# Main_Board_Tank.net
KiCad netlist of a schematic drawn in Altium Designer
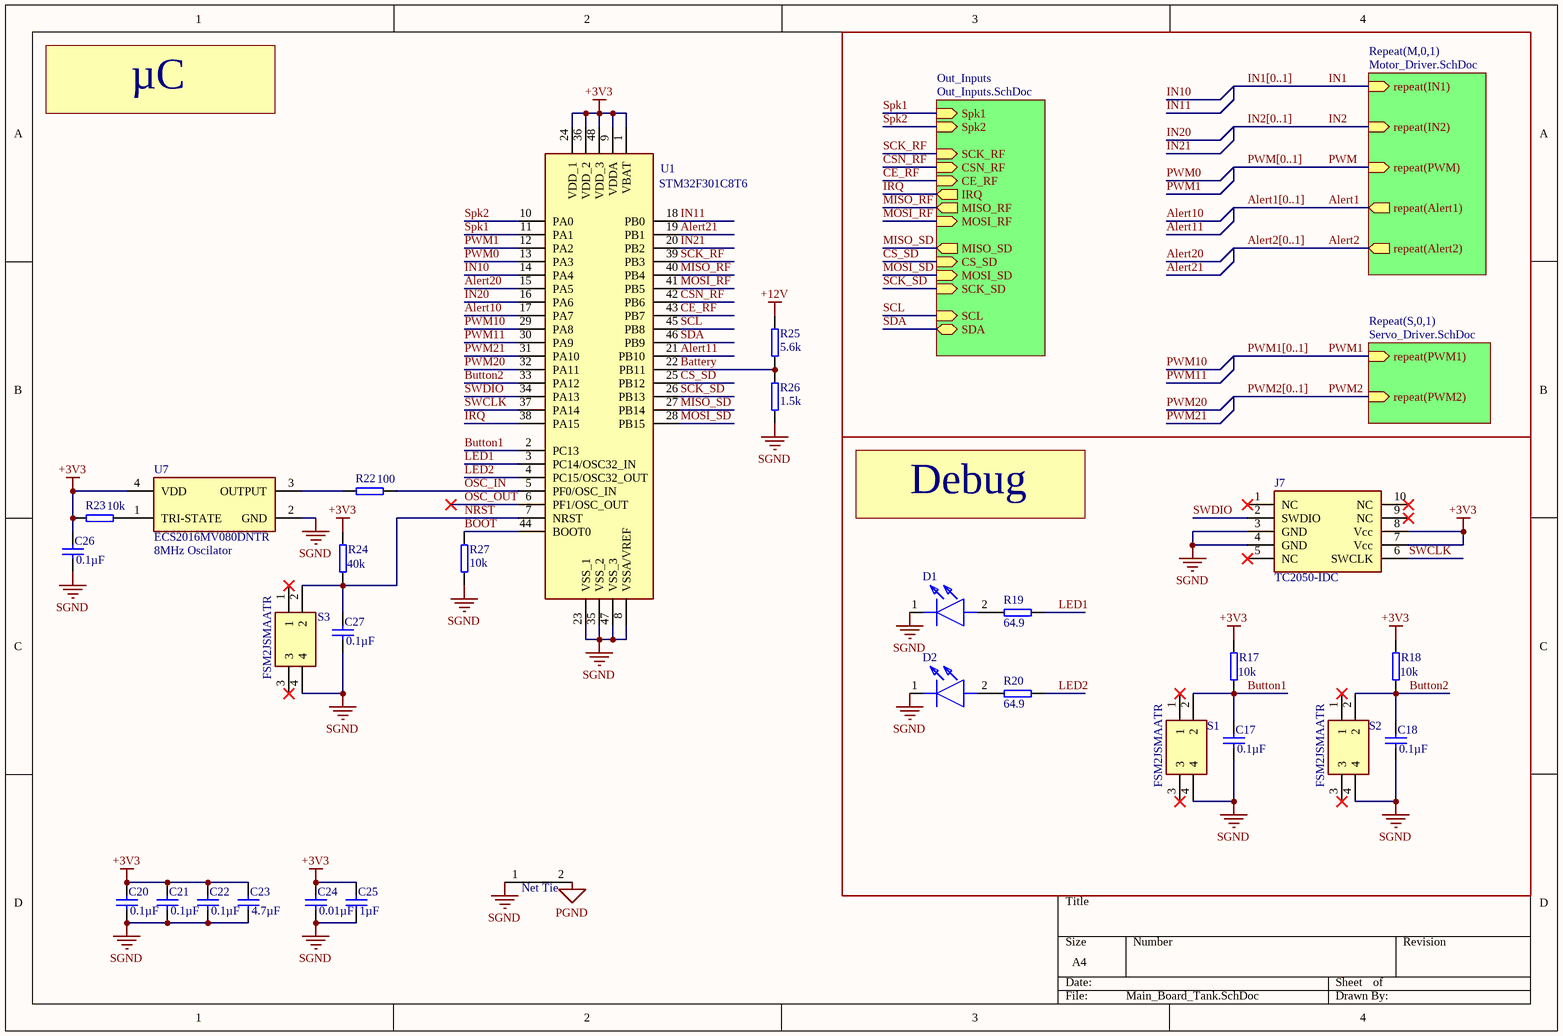
[diagram p0: Main_Board_Tank.SchDoc]

(export (version "E")
  (design (tool "Eeschema 10.0.6"))
  (components
    (comp (ref "C17")
      (value "0.1µF")
      (footprint "Capacitor 0603")
      (description "Capacitor")
      (libsource (lib "Schematic_Lib") (part "Capacitor 0603"))
    )
    (comp (ref "C18")
      (value "0.1µF")
      (footprint "Capacitor 0603")
      (description "Capacitor")
      (libsource (lib "Schematic_Lib") (part "Capacitor 0603"))
    )
    (comp (ref "C20")
      (value "0.1µF")
      (footprint "Capacitor 0603")
      (description "Capacitor")
      (libsource (lib "Schematic_Lib") (part "Capacitor 0603"))
    )
    (comp (ref "C21")
      (value "0.1µF")
      (footprint "Capacitor 0603")
      (description "Capacitor")
      (libsource (lib "Schematic_Lib") (part "Capacitor 0603"))
    )
    (comp (ref "C22")
      (value "0.1µF")
      (footprint "Capacitor 0603")
      (description "Capacitor")
      (libsource (lib "Schematic_Lib") (part "Capacitor 0603"))
    )
    (comp (ref "C23")
      (value "4.7µF")
      (footprint "Capacitor 0603")
      (description "Capacitor")
      (libsource (lib "Schematic_Lib") (part "Capacitor 0603"))
    )
    (comp (ref "C24")
      (value "0.01µF")
      (footprint "Capacitor 0603")
      (description "Capacitor")
      (libsource (lib "Schematic_Lib") (part "Capacitor 0603"))
    )
    (comp (ref "C25")
      (value "1µF")
      (footprint "Capacitor 0603")
      (description "Capacitor")
      (libsource (lib "Schematic_Lib") (part "Capacitor 0603"))
    )
    (comp (ref "C26")
      (value "0.1µF")
      (footprint "Capacitor 0603")
      (description "Capacitor")
      (libsource (lib "Schematic_Lib") (part "Capacitor 0603"))
    )
    (comp (ref "C27")
      (value "0.1µF")
      (footprint "Capacitor 0603")
      (description "Capacitor")
      (libsource (lib "Schematic_Lib") (part "Capacitor 0603"))
    )
    (comp (ref "D1")
      (value "LED 1608 (0603) SMD")
      (footprint "INS21AT2G")
      (libsource (lib "Schematic_Lib") (part "LED 1608 (0603) SMD"))
    )
    (comp (ref "D2")
      (value "LED 1608 (0603) SMD")
      (footprint "INS21AT2G")
      (libsource (lib "Schematic_Lib") (part "LED 1608 (0603) SMD"))
    )
    (comp (ref "J7")
      (value "TC2050-IDC")
      (footprint "TAG-CONNECT_TC2050-IDC")
      (description "CBL PLUG-OF-NAILS 10-PIN W/LEGS")
      (fields (field (name "MF") "Tag-Connect LLC") (field (name "DIGI-KEY_PART_NUMBER") "TC2050-IDC-ND"))
      (libsource (lib "Schematic_Lib") (part "TC2050-IDC"))
    )
    (comp (ref "NT1")
      (value "Net Tie")
      (footprint "Net_Tie")
      (libsource (lib "Schematic_Lib") (part "Net Tie"))
    )
    (comp (ref "R17")
      (value "10k")
      (footprint "Resistor 0603")
      (description "Resistor")
      (libsource (lib "Schematic_Lib") (part "Resistor 0603"))
    )
    (comp (ref "R18")
      (value "10k")
      (footprint "Resistor 0603")
      (description "Resistor")
      (libsource (lib "Schematic_Lib") (part "Resistor 0603"))
    )
    (comp (ref "R19")
      (value "64.9")
      (footprint "Resistor 0603")
      (description "Resistor")
      (libsource (lib "Schematic_Lib") (part "Resistor 0603"))
    )
    (comp (ref "R20")
      (value "64.9")
      (footprint "Resistor 0603")
      (description "Resistor")
      (libsource (lib "Schematic_Lib") (part "Resistor 0603"))
    )
    (comp (ref "R22")
      (value "100")
      (footprint "Resistor 0603")
      (description "Resistor")
      (libsource (lib "Schematic_Lib") (part "Resistor 0603"))
    )
    (comp (ref "R23")
      (value "10k")
      (footprint "Resistor 0603")
      (description "Resistor")
      (libsource (lib "Schematic_Lib") (part "Resistor 0603"))
    )
    (comp (ref "R24")
      (value "40k")
      (footprint "Resistor 0603")
      (description "Resistor")
      (libsource (lib "Schematic_Lib") (part "Resistor 0603"))
    )
    (comp (ref "R25")
      (value "5.6k")
      (footprint "Resistor 0603")
      (description "Resistor")
      (libsource (lib "Schematic_Lib") (part "Resistor 0603"))
    )
    (comp (ref "R26")
      (value "1.5k")
      (footprint "Resistor 0603")
      (description "Resistor")
      (libsource (lib "Schematic_Lib") (part "Resistor 0603"))
    )
    (comp (ref "R27")
      (value "10k")
      (footprint "Resistor 0603")
      (description "Resistor")
      (libsource (lib "Schematic_Lib") (part "Resistor 0603"))
    )
    (comp (ref "S1")
      (value "FSM2JSMAATR")
      (footprint "FSM2J_1")
      (description "Switch")
      (fields (field (name "MOUSER PART NUMBER") "506-FSM2JSMAATR"))
      (libsource (lib "Schematic_Lib") (part "FSM2JSMAATR"))
    )
    (comp (ref "S2")
      (value "FSM2JSMAATR")
      (footprint "FSM2J_1")
      (description "Switch")
      (fields (field (name "MOUSER PART NUMBER") "506-FSM2JSMAATR"))
      (libsource (lib "Schematic_Lib") (part "FSM2JSMAATR"))
    )
    (comp (ref "S3")
      (value "FSM2JSMAATR")
      (footprint "FSM2J_1")
      (description "Switch")
      (fields (field (name "MOUSER PART NUMBER") "506-FSM2JSMAATR"))
      (libsource (lib "Schematic_Lib") (part "FSM2JSMAATR"))
    )
    (comp (ref "U1")
      (value "STM32F301C8T6")
      (footprint "QFP50P900X900X160-48N")
      (description "STMICROELECTRONICS - STM32F301C8T6 - MCU, 32BIT, CORTEX-M4, 72MHZ, LQFP-48")
      (fields (field (name "MOUSER PART NUMBER") "511-STM32F301C8T6"))
      (libsource (lib "Schematic_Lib") (part "STM32F301C8T6"))
    )
    (comp (ref "U7")
      (value "ECS2016MV080DNTR")
      (footprint "OSC_ECS-1618-300-BN-TR")
      (description "25 MHz XO (Standard) HCMOS Oscillator 1.8V ~ 3.3V Enable/Disable 4-SMD, No Lead")
      (fields (field (name "MF") "ECS Inc.") (field (name "MP") "ECS-2016MV-250-CN-TR3"))
      (libsource (lib "Schematic_Lib") (part "ECS-2016MV-250-CN-TR3"))
    )
  )
  (nets
    (net (code "1") (name "+3V3") (class "Default")
      (node (ref "C20") (pin "1") (pinfunction "1_1") (pintype "passive"))
      (node (ref "C21") (pin "1") (pinfunction "1_1") (pintype "passive"))
      (node (ref "C22") (pin "1") (pinfunction "1_1") (pintype "passive"))
      (node (ref "C23") (pin "1") (pinfunction "1_1") (pintype "passive"))
      (node (ref "C24") (pin "1") (pinfunction "1_1") (pintype "passive"))
      (node (ref "C25") (pin "1") (pinfunction "1_1") (pintype "passive"))
      (node (ref "C26") (pin "1") (pinfunction "1_1") (pintype "passive"))
      (node (ref "J7") (pin "7") (pinfunction "Vcc_7") (pintype "passive"))
      (node (ref "J7") (pin "8") (pinfunction "Vcc_8") (pintype "passive"))
      (node (ref "R17") (pin "1") (pintype "passive"))
      (node (ref "R18") (pin "1") (pintype "passive"))
      (node (ref "R23") (pin "2") (pintype "passive"))
      (node (ref "R24") (pin "1") (pintype "passive"))
      (node (ref "U1") (pin "1") (pinfunction "VBAT_1") (pintype "passive"))
      (node (ref "U1") (pin "24") (pinfunction "VDD_1_24") (pintype "passive"))
      (node (ref "U1") (pin "36") (pinfunction "VDD_2_36") (pintype "passive"))
      (node (ref "U1") (pin "48") (pinfunction "VDD_3_48") (pintype "passive"))
      (node (ref "U1") (pin "9") (pinfunction "VDDA_9") (pintype "passive"))
      (node (ref "U7") (pin "4") (pinfunction "VDD_4") (pintype "passive"))
    )
    (net (code "2") (name "+12V") (class "Default") (node (ref "R25") (pin "2") (pintype "passive")))
    (net (code "7") (name "/Alert10") (class "Default")
      (node (ref "U1") (pin "17") (pinfunction "PA7_17") (pintype "passive"))
    )
    (net (code "8") (name "/Alert11") (class "Default")
      (node (ref "U1") (pin "21") (pinfunction "PB10_21") (pintype "passive"))
    )
    (net (code "9") (name "/Alert20") (class "Default")
      (node (ref "U1") (pin "15") (pinfunction "PA5_15") (pintype "passive"))
    )
    (net (code "10") (name "/Alert21") (class "Default")
      (node (ref "U1") (pin "19") (pinfunction "PB1_19") (pintype "passive"))
    )
    (net (code "11") (name "/BOOT") (class "Default")
      (node (ref "R27") (pin "2") (pintype "passive"))
      (node (ref "U1") (pin "44") (pinfunction "BOOT0_44") (pintype "passive"))
    )
    (net (code "12") (name "/Battery") (class "Default")
      (node (ref "R25") (pin "1") (pintype "passive"))
      (node (ref "R26") (pin "2") (pintype "passive"))
      (node (ref "U1") (pin "22") (pinfunction "PB11_22") (pintype "passive"))
    )
    (net (code "13") (name "/Button1") (class "Default")
      (node (ref "C17") (pin "1") (pinfunction "1_1") (pintype "passive"))
      (node (ref "R17") (pin "2") (pintype "passive"))
      (node (ref "S1") (pin "2") (pinfunction "2_2") (pintype "passive"))
      (node (ref "U1") (pin "2") (pinfunction "PC13_2") (pintype "passive"))
    )
    (net (code "14") (name "/Button2") (class "Default")
      (node (ref "C18") (pin "1") (pinfunction "1_1") (pintype "passive"))
      (node (ref "R18") (pin "2") (pintype "passive"))
      (node (ref "S2") (pin "2") (pinfunction "2_2") (pintype "passive"))
      (node (ref "U1") (pin "33") (pinfunction "PA12_33") (pintype "passive"))
    )
    (net (code "15") (name "/CE_RF") (class "Default")
      (node (ref "U1") (pin "43") (pinfunction "PB7_43") (pintype "passive"))
    )
    (net (code "16") (name "/CSN_RF") (class "Default")
      (node (ref "U1") (pin "42") (pinfunction "PB6_42") (pintype "passive"))
    )
    (net (code "17") (name "/CS_SD") (class "Default")
      (node (ref "U1") (pin "25") (pinfunction "PB12_25") (pintype "passive"))
    )
    (net (code "22") (name "/IN10") (class "Default")
      (node (ref "U1") (pin "14") (pinfunction "PA4_14") (pintype "passive"))
    )
    (net (code "23") (name "/IN11") (class "Default")
      (node (ref "U1") (pin "18") (pinfunction "PB0_18") (pintype "passive"))
    )
    (net (code "24") (name "/IN20") (class "Default")
      (node (ref "U1") (pin "16") (pinfunction "PA6_16") (pintype "passive"))
    )
    (net (code "25") (name "/IN21") (class "Default")
      (node (ref "U1") (pin "20") (pinfunction "PB2_20") (pintype "passive"))
    )
    (net (code "26") (name "/IRQ") (class "Default")
      (node (ref "U1") (pin "38") (pinfunction "PA15_38") (pintype "passive"))
    )
    (net (code "27") (name "/LED1") (class "Default")
      (node (ref "R19") (pin "1") (pintype "passive"))
      (node (ref "U1") (pin "3") (pinfunction "PC14/OSC32_IN_3") (pintype "passive"))
    )
    (net (code "28") (name "/LED2") (class "Default")
      (node (ref "R20") (pin "1") (pintype "passive"))
      (node (ref "U1") (pin "4") (pinfunction "PC15/OSC32_OUT_4") (pintype "passive"))
    )
    (net (code "29") (name "/MISO_RF") (class "Default")
      (node (ref "U1") (pin "40") (pinfunction "PB4_40") (pintype "passive"))
    )
    (net (code "30") (name "/MISO_SD") (class "Default")
      (node (ref "U1") (pin "27") (pinfunction "PB14_27") (pintype "passive"))
    )
    (net (code "31") (name "/MOSI_RF") (class "Default")
      (node (ref "U1") (pin "41") (pinfunction "PB5_41") (pintype "passive"))
    )
    (net (code "32") (name "/MOSI_SD") (class "Default")
      (node (ref "U1") (pin "28") (pinfunction "PB15_28") (pintype "passive"))
    )
    (net (code "33") (name "/NRST") (class "Default")
      (node (ref "C27") (pin "1") (pinfunction "1_1") (pintype "passive"))
      (node (ref "R24") (pin "2") (pintype "passive"))
      (node (ref "S3") (pin "2") (pinfunction "2_2") (pintype "passive"))
      (node (ref "U1") (pin "7") (pinfunction "NRST_7") (pintype "passive"))
    )
    (net (code "34") (name "/OSC_IN") (class "Default")
      (node (ref "R22") (pin "1") (pintype "passive"))
      (node (ref "U1") (pin "5") (pinfunction "PF0/OSC_IN_5") (pintype "passive"))
    )
    (net (code "35") (name "/OSC_OUT") (class "Default")
      (node (ref "U1") (pin "6") (pinfunction "PF1/OSC_OUT_6") (pintype "passive+no_connect"))
    )
    (net (code "37") (name "/PWM0") (class "Default")
      (node (ref "U1") (pin "13") (pinfunction "PA3_13") (pintype "passive"))
    )
    (net (code "38") (name "/PWM1") (class "Default")
      (node (ref "U1") (pin "12") (pinfunction "PA2_12") (pintype "passive"))
    )
    (net (code "42") (name "/PWM10") (class "Default")
      (node (ref "U1") (pin "29") (pinfunction "PA8_29") (pintype "passive"))
    )
    (net (code "43") (name "/PWM11") (class "Default")
      (node (ref "U1") (pin "30") (pinfunction "PA9_30") (pintype "passive"))
    )
    (net (code "44") (name "/PWM20") (class "Default")
      (node (ref "U1") (pin "32") (pinfunction "PA11_32") (pintype "passive"))
    )
    (net (code "45") (name "/PWM21") (class "Default")
      (node (ref "U1") (pin "31") (pinfunction "PA10_31") (pintype "passive"))
    )
    (net (code "47") (name "/SCK_RF") (class "Default")
      (node (ref "U1") (pin "39") (pinfunction "PB3_39") (pintype "passive"))
    )
    (net (code "48") (name "/SCK_SD") (class "Default")
      (node (ref "U1") (pin "26") (pinfunction "PB13_26") (pintype "passive"))
    )
    (net (code "49") (name "/SCL") (class "Default")
      (node (ref "U1") (pin "45") (pinfunction "PB8_45") (pintype "passive"))
    )
    (net (code "50") (name "/SDA") (class "Default")
      (node (ref "U1") (pin "46") (pinfunction "PB9_46") (pintype "passive"))
    )
    (net (code "51") (name "/SWCLK") (class "Default")
      (node (ref "J7") (pin "6") (pinfunction "SWCLK_6") (pintype "passive"))
      (node (ref "U1") (pin "37") (pinfunction "PA14_37") (pintype "passive"))
    )
    (net (code "52") (name "/SWDIO") (class "Default")
      (node (ref "J7") (pin "2") (pinfunction "SWDIO_2") (pintype "passive"))
      (node (ref "U1") (pin "34") (pinfunction "PA13_34") (pintype "passive"))
    )
    (net (code "53") (name "/Spk1") (class "Default")
      (node (ref "U1") (pin "11") (pinfunction "PA1_11") (pintype "passive"))
    )
    (net (code "54") (name "/Spk2") (class "Default")
      (node (ref "U1") (pin "10") (pinfunction "PA0_10") (pintype "passive"))
    )
    (net (code "55") (name "Net-(D1-A)") (class "Default")
      (node (ref "D1") (pin "2") (pinfunction "A_2") (pintype "passive"))
      (node (ref "R19") (pin "2") (pintype "passive"))
    )
    (net (code "56") (name "Net-(D2-A)") (class "Default")
      (node (ref "D2") (pin "2") (pinfunction "A_2") (pintype "passive"))
      (node (ref "R20") (pin "2") (pintype "passive"))
    )
    (net (code "57") (name "Net-(U7-OUTPUT)") (class "Default")
      (node (ref "R22") (pin "2") (pintype "passive"))
      (node (ref "U7") (pin "3") (pinfunction "OUTPUT_3") (pintype "passive"))
    )
    (net (code "58") (name "Net-(U7-TRI-STATE)") (class "Default")
      (node (ref "R23") (pin "1") (pintype "passive"))
      (node (ref "U7") (pin "1") (pinfunction "TRI-STATE_1") (pintype "passive"))
    )
    (net (code "59") (name "PGND") (class "Default")
      (node (ref "NT1") (pin "2") (pinfunction "2_2") (pintype "power_in"))
    )
    (net (code "60") (name "SGND") (class "Default")
      (node (ref "C17") (pin "2") (pinfunction "2_2") (pintype "passive"))
      (node (ref "C18") (pin "2") (pinfunction "2_2") (pintype "passive"))
      (node (ref "C20") (pin "2") (pinfunction "2_2") (pintype "passive"))
      (node (ref "C21") (pin "2") (pinfunction "2_2") (pintype "passive"))
      (node (ref "C22") (pin "2") (pinfunction "2_2") (pintype "passive"))
      (node (ref "C23") (pin "2") (pinfunction "2_2") (pintype "passive"))
      (node (ref "C24") (pin "2") (pinfunction "2_2") (pintype "passive"))
      (node (ref "C25") (pin "2") (pinfunction "2_2") (pintype "passive"))
      (node (ref "C26") (pin "2") (pinfunction "2_2") (pintype "passive"))
      (node (ref "C27") (pin "2") (pinfunction "2_2") (pintype "passive"))
      (node (ref "D1") (pin "1") (pinfunction "K_1") (pintype "passive"))
      (node (ref "D2") (pin "1") (pinfunction "K_1") (pintype "passive"))
      (node (ref "J7") (pin "3") (pinfunction "GND_3") (pintype "passive"))
      (node (ref "J7") (pin "4") (pinfunction "GND_4") (pintype "passive"))
      (node (ref "NT1") (pin "1") (pinfunction "1_1") (pintype "power_in"))
      (node (ref "R26") (pin "1") (pintype "passive"))
      (node (ref "R27") (pin "1") (pintype "passive"))
      (node (ref "S1") (pin "4") (pinfunction "4_4") (pintype "passive"))
      (node (ref "S2") (pin "4") (pinfunction "4_4") (pintype "passive"))
      (node (ref "S3") (pin "4") (pinfunction "4_4") (pintype "passive"))
      (node (ref "U1") (pin "23") (pinfunction "VSS_1_23") (pintype "passive"))
      (node (ref "U1") (pin "35") (pinfunction "VSS_2_35") (pintype "passive"))
      (node (ref "U1") (pin "47") (pinfunction "VSS_3_47") (pintype "passive"))
      (node (ref "U1") (pin "8") (pinfunction "VSSA/VREF_8") (pintype "passive"))
      (node (ref "U7") (pin "2") (pinfunction "GND_2") (pintype "power_in"))
    )
    (net (code "61") (name "unconnected-(J7-NC-Pad1)") (class "Default")
      (node (ref "J7") (pin "1") (pinfunction "NC_1") (pintype "passive+no_connect"))
    )
    (net (code "62") (name "unconnected-(J7-NC-Pad5)") (class "Default")
      (node (ref "J7") (pin "5") (pinfunction "NC_5") (pintype "passive+no_connect"))
    )
    (net (code "63") (name "unconnected-(J7-NC-Pad9)") (class "Default")
      (node (ref "J7") (pin "9") (pinfunction "NC_9") (pintype "passive+no_connect"))
    )
    (net (code "64") (name "unconnected-(J7-NC-Pad10)") (class "Default")
      (node (ref "J7") (pin "10") (pinfunction "NC_10") (pintype "passive+no_connect"))
    )
    (net (code "65") (name "unconnected-(S1-Pad1)") (class "Default")
      (node (ref "S1") (pin "1") (pinfunction "1_1") (pintype "passive+no_connect"))
    )
    (net (code "66") (name "unconnected-(S1-Pad3)") (class "Default")
      (node (ref "S1") (pin "3") (pinfunction "3_3") (pintype "passive+no_connect"))
    )
    (net (code "67") (name "unconnected-(S2-Pad1)") (class "Default")
      (node (ref "S2") (pin "1") (pinfunction "1_1") (pintype "passive+no_connect"))
    )
    (net (code "68") (name "unconnected-(S2-Pad3)") (class "Default")
      (node (ref "S2") (pin "3") (pinfunction "3_3") (pintype "passive+no_connect"))
    )
    (net (code "69") (name "unconnected-(S3-Pad1)") (class "Default")
      (node (ref "S3") (pin "1") (pinfunction "1_1") (pintype "passive+no_connect"))
    )
    (net (code "70") (name "unconnected-(S3-Pad3)") (class "Default")
      (node (ref "S3") (pin "3") (pinfunction "3_3") (pintype "passive+no_connect"))
    )
  )
)
